# schematic.net
KiCad netlist of a schematic drawn in EAGLE
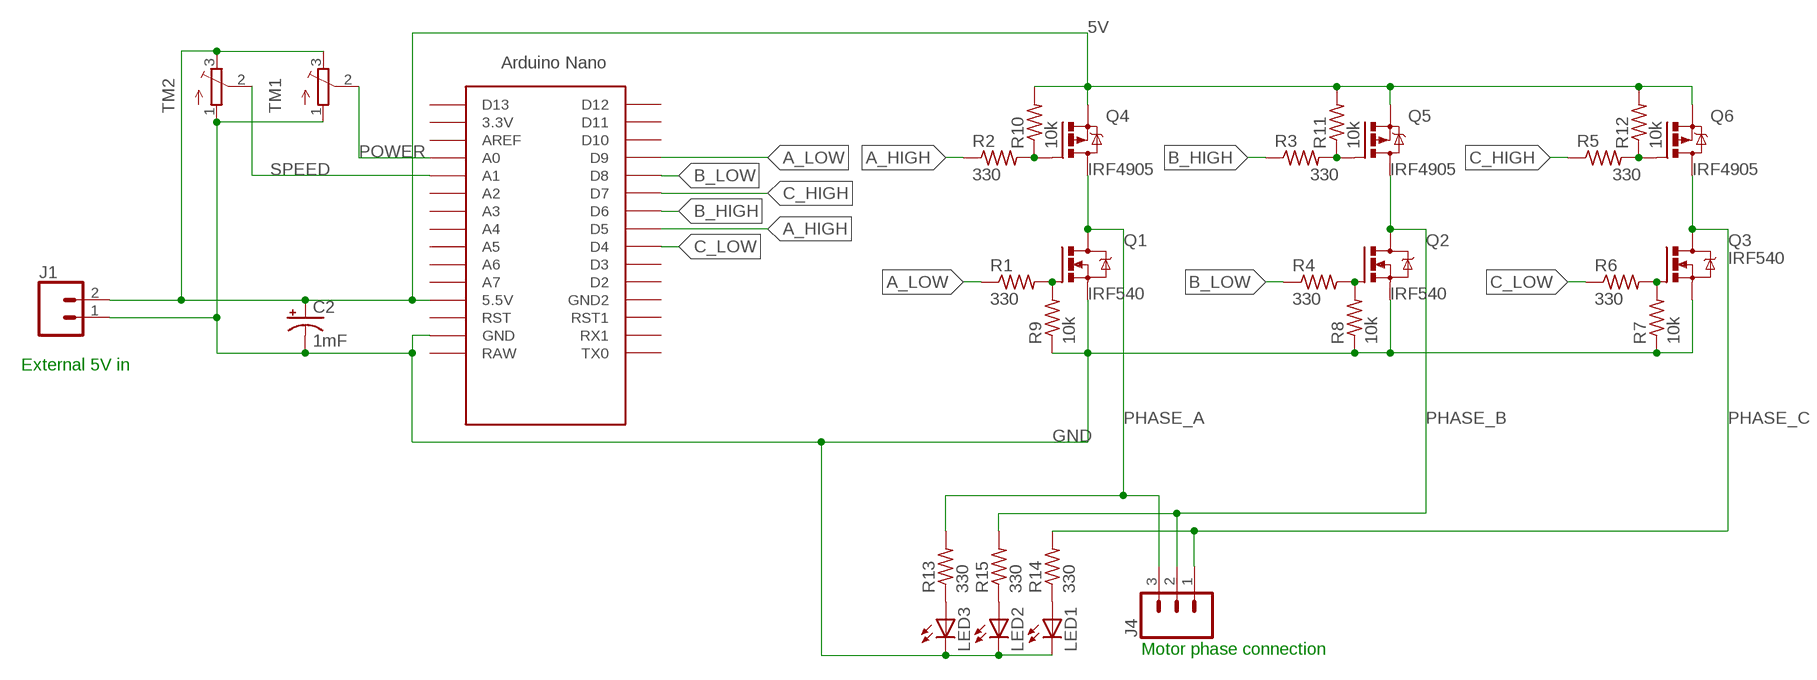
[diagram p0: schematic, sheet 1]

(export (version "E")
  (design (tool "Eeschema 10.0.6"))
  (components
    (comp (ref "C2")
      (value "1mF")
      (footprint "eagle-import:CPOL-RADIAL-5MM-10MM")
      (libsource (lib "eagle-import") (part "1000UF-RADIAL-5MM-25V-20%"))
    )
    (comp (ref "J1")
      (value "CONN_025MM")
      (footprint "eagle-import:SCREWTERMINAL-5MM-2")
      (libsource (lib "eagle-import") (part "CONN_025MM"))
    )
    (comp (ref "J4")
      (value "CONN_03-SCREW-5MM")
      (footprint "eagle-import:SCREWTERMINAL-5MM-3")
      (libsource (lib "eagle-import") (part "CONN_03-SCREW-5MM"))
    )
    (comp (ref "LED1")
      (value "LED5MM")
      (footprint "eagle-import:LED5MM")
      (libsource (lib "eagle-import") (part "LED5MM"))
    )
    (comp (ref "LED2")
      (value "LED5MM")
      (footprint "eagle-import:LED5MM")
      (libsource (lib "eagle-import") (part "LED5MM"))
    )
    (comp (ref "LED3")
      (value "LED5MM")
      (footprint "eagle-import:LED5MM")
      (libsource (lib "eagle-import") (part "LED5MM"))
    )
    (comp (ref "Q1")
      (value "IRF540")
      (footprint "eagle-import:TO220BV")
      (libsource (lib "eagle-import") (part "IRF540"))
    )
    (comp (ref "Q2")
      (value "IRF540")
      (footprint "eagle-import:TO220BV")
      (libsource (lib "eagle-import") (part "IRF540"))
    )
    (comp (ref "Q3")
      (value "IRF540")
      (footprint "eagle-import:TO220BV")
      (libsource (lib "eagle-import") (part "IRF540"))
    )
    (comp (ref "Q4")
      (value "IRF4905")
      (footprint "eagle-import:TO220BH")
      (libsource (lib "eagle-import") (part "IRF4905"))
    )
    (comp (ref "Q5")
      (value "IRF4905")
      (footprint "eagle-import:TO220BH")
      (libsource (lib "eagle-import") (part "IRF4905"))
    )
    (comp (ref "Q6")
      (value "IRF4905")
      (footprint "eagle-import:TO220BH")
      (libsource (lib "eagle-import") (part "IRF4905"))
    )
    (comp (ref "R1")
      (value "330")
      (footprint "eagle-import:0204_5")
      (libsource (lib "eagle-import") (part "R-US_0204/5"))
    )
    (comp (ref "R2")
      (value "330")
      (footprint "eagle-import:0204_5")
      (libsource (lib "eagle-import") (part "R-US_0204/5"))
    )
    (comp (ref "R3")
      (value "330")
      (footprint "eagle-import:0204_5")
      (libsource (lib "eagle-import") (part "R-US_0204/5"))
    )
    (comp (ref "R4")
      (value "330")
      (footprint "eagle-import:0204_5")
      (libsource (lib "eagle-import") (part "R-US_0204/5"))
    )
    (comp (ref "R5")
      (value "330")
      (footprint "eagle-import:0204_5")
      (libsource (lib "eagle-import") (part "R-US_0204/5"))
    )
    (comp (ref "R6")
      (value "330")
      (footprint "eagle-import:0204_5")
      (libsource (lib "eagle-import") (part "R-US_0204/5"))
    )
    (comp (ref "R7")
      (value "10k")
      (footprint "eagle-import:0204_5")
      (libsource (lib "eagle-import") (part "R-US_0204/5"))
    )
    (comp (ref "R8")
      (value "10k")
      (footprint "eagle-import:0204_5")
      (libsource (lib "eagle-import") (part "R-US_0204/5"))
    )
    (comp (ref "R9")
      (value "10k")
      (footprint "eagle-import:0204_5")
      (libsource (lib "eagle-import") (part "R-US_0204/5"))
    )
    (comp (ref "R10")
      (value "10k")
      (footprint "eagle-import:0204_5")
      (libsource (lib "eagle-import") (part "R-US_0204/5"))
    )
    (comp (ref "R11")
      (value "10k")
      (footprint "eagle-import:0204_5")
      (libsource (lib "eagle-import") (part "R-US_0204/5"))
    )
    (comp (ref "R12")
      (value "10k")
      (footprint "eagle-import:0204_5")
      (libsource (lib "eagle-import") (part "R-US_0204/5"))
    )
    (comp (ref "R13")
      (value "330")
      (footprint "eagle-import:0204_5")
      (libsource (lib "eagle-import") (part "R-US_0204/5"))
    )
    (comp (ref "R14")
      (value "330")
      (footprint "eagle-import:0204_5")
      (libsource (lib "eagle-import") (part "R-US_0204/5"))
    )
    (comp (ref "R15")
      (value "330")
      (footprint "eagle-import:0204_5")
      (libsource (lib "eagle-import") (part "R-US_0204/5"))
    )
    (comp (ref "TM1")
      (value "TRIMPOT3386")
      (footprint "eagle-import:TRIM-3386")
      (libsource (lib "eagle-import") (part "TRIMPOT3386"))
    )
    (comp (ref "TM2")
      (value "TRIMPOT3386")
      (footprint "eagle-import:TRIM-3386")
      (libsource (lib "eagle-import") (part "TRIMPOT3386"))
    )
    (comp (ref "U$1")
      (value "NANO")
      (footprint "eagle-import:NANO")
      (libsource (lib "eagle-import") (part "NANO"))
    )
  )
  (nets
    (net (code "1") (name "/5V") (class "Default")
      (node (ref "C2") (pin "+") (pinfunction "+_+") (pintype "passive"))
      (node (ref "J1") (pin "2") (pinfunction "2_2") (pintype "passive"))
      (node (ref "Q4") (pin "S") (pinfunction "S_S") (pintype "passive"))
      (node (ref "Q5") (pin "S") (pinfunction "S_S") (pintype "passive"))
      (node (ref "Q6") (pin "S") (pinfunction "S_S") (pintype "passive"))
      (node (ref "R10") (pin "2") (pinfunction "2_2") (pintype "passive"))
      (node (ref "R11") (pin "2") (pinfunction "2_2") (pintype "passive"))
      (node (ref "R12") (pin "2") (pinfunction "2_2") (pintype "passive"))
      (node (ref "TM1") (pin "3") (pinfunction "E_3") (pintype "passive"))
      (node (ref "TM2") (pin "3") (pinfunction "E_3") (pintype "passive"))
      (node (ref "U$1") (pin "5V") (pinfunction "5.5V_5V") (pintype "bidirectional"))
    )
    (net (code "2") (name "/GND") (class "Default")
      (node (ref "C2") (pin "-") (pinfunction "-_-") (pintype "passive"))
      (node (ref "J1") (pin "1") (pinfunction "1_1") (pintype "passive"))
      (node (ref "LED1") (pin "K") (pinfunction "C_K") (pintype "passive"))
      (node (ref "LED2") (pin "K") (pinfunction "C_K") (pintype "passive"))
      (node (ref "LED3") (pin "K") (pinfunction "C_K") (pintype "passive"))
      (node (ref "Q1") (pin "S") (pinfunction "S_S") (pintype "passive"))
      (node (ref "Q2") (pin "S") (pinfunction "S_S") (pintype "passive"))
      (node (ref "Q3") (pin "S") (pinfunction "S_S") (pintype "passive"))
      (node (ref "R7") (pin "1") (pinfunction "1_1") (pintype "passive"))
      (node (ref "R8") (pin "1") (pinfunction "1_1") (pintype "passive"))
      (node (ref "R9") (pin "1") (pinfunction "1_1") (pintype "passive"))
      (node (ref "TM1") (pin "1") (pinfunction "A_1") (pintype "passive"))
      (node (ref "TM2") (pin "1") (pinfunction "A_1") (pintype "passive"))
      (node (ref "U$1") (pin "GND") (pinfunction "GND_GND") (pintype "bidirectional"))
    )
    (net (code "3") (name "/PHASE_A") (class "Default")
      (node (ref "J4") (pin "3") (pinfunction "3_3") (pintype "passive"))
      (node (ref "Q1") (pin "D") (pinfunction "D_D") (pintype "passive"))
      (node (ref "Q4") (pin "D") (pinfunction "D_D") (pintype "passive"))
      (node (ref "R13") (pin "2") (pinfunction "2_2") (pintype "passive"))
    )
    (net (code "4") (name "/PHASE_B") (class "Default")
      (node (ref "J4") (pin "2") (pinfunction "2_2") (pintype "passive"))
      (node (ref "Q2") (pin "D") (pinfunction "D_D") (pintype "passive"))
      (node (ref "Q5") (pin "D") (pinfunction "D_D") (pintype "passive"))
      (node (ref "R15") (pin "2") (pinfunction "2_2") (pintype "passive"))
    )
    (net (code "5") (name "/PHASE_C") (class "Default")
      (node (ref "J4") (pin "1") (pinfunction "1_1") (pintype "passive"))
      (node (ref "Q3") (pin "D") (pinfunction "D_D") (pintype "passive"))
      (node (ref "Q6") (pin "D") (pinfunction "D_D") (pintype "passive"))
      (node (ref "R14") (pin "2") (pinfunction "2_2") (pintype "passive"))
    )
    (net (code "6") (name "/POWER") (class "Default")
      (node (ref "TM1") (pin "2") (pinfunction "S_2") (pintype "passive"))
      (node (ref "U$1") (pin "A0") (pinfunction "A0_A0") (pintype "bidirectional"))
    )
    (net (code "7") (name "/SPEED") (class "Default")
      (node (ref "TM2") (pin "2") (pinfunction "S_2") (pintype "passive"))
      (node (ref "U$1") (pin "A1") (pinfunction "A1_A1") (pintype "bidirectional"))
    )
    (net (code "8") (name "A_HIGH") (class "Default")
      (node (ref "R2") (pin "1") (pinfunction "1_1") (pintype "passive"))
      (node (ref "U$1") (pin "D5") (pinfunction "D5_D5") (pintype "bidirectional"))
    )
    (net (code "9") (name "A_LOW") (class "Default")
      (node (ref "R1") (pin "1") (pinfunction "1_1") (pintype "passive"))
      (node (ref "U$1") (pin "D9") (pinfunction "D9_D9") (pintype "bidirectional"))
    )
    (net (code "10") (name "B_HIGH") (class "Default")
      (node (ref "R3") (pin "1") (pinfunction "1_1") (pintype "passive"))
      (node (ref "U$1") (pin "D6") (pinfunction "D6_D6") (pintype "bidirectional"))
    )
    (net (code "11") (name "B_LOW") (class "Default")
      (node (ref "R4") (pin "1") (pinfunction "1_1") (pintype "passive"))
      (node (ref "U$1") (pin "D8") (pinfunction "D8_D8") (pintype "bidirectional"))
    )
    (net (code "12") (name "C_HIGH") (class "Default")
      (node (ref "R5") (pin "1") (pinfunction "1_1") (pintype "passive"))
      (node (ref "U$1") (pin "D7") (pinfunction "D7_D7") (pintype "bidirectional"))
    )
    (net (code "13") (name "C_LOW") (class "Default")
      (node (ref "R6") (pin "1") (pinfunction "1_1") (pintype "passive"))
      (node (ref "U$1") (pin "D4") (pinfunction "D4_D4") (pintype "bidirectional"))
    )
    (net (code "14") (name "Net-(LED1-PadA)") (class "Default")
      (node (ref "LED1") (pin "A") (pinfunction "A_A") (pintype "passive"))
      (node (ref "R14") (pin "1") (pinfunction "1_1") (pintype "passive"))
    )
    (net (code "15") (name "Net-(LED2-PadA)") (class "Default")
      (node (ref "LED2") (pin "A") (pinfunction "A_A") (pintype "passive"))
      (node (ref "R15") (pin "1") (pinfunction "1_1") (pintype "passive"))
    )
    (net (code "16") (name "Net-(LED3-PadA)") (class "Default")
      (node (ref "LED3") (pin "A") (pinfunction "A_A") (pintype "passive"))
      (node (ref "R13") (pin "1") (pinfunction "1_1") (pintype "passive"))
    )
    (net (code "17") (name "Net-(Q1-PadG)") (class "Default")
      (node (ref "Q1") (pin "G") (pinfunction "G_G") (pintype "passive"))
      (node (ref "R1") (pin "2") (pinfunction "2_2") (pintype "passive"))
      (node (ref "R9") (pin "2") (pinfunction "2_2") (pintype "passive"))
    )
    (net (code "18") (name "Net-(Q2-PadG)") (class "Default")
      (node (ref "Q2") (pin "G") (pinfunction "G_G") (pintype "passive"))
      (node (ref "R4") (pin "2") (pinfunction "2_2") (pintype "passive"))
      (node (ref "R8") (pin "2") (pinfunction "2_2") (pintype "passive"))
    )
    (net (code "19") (name "Net-(Q3-PadG)") (class "Default")
      (node (ref "Q3") (pin "G") (pinfunction "G_G") (pintype "passive"))
      (node (ref "R6") (pin "2") (pinfunction "2_2") (pintype "passive"))
      (node (ref "R7") (pin "2") (pinfunction "2_2") (pintype "passive"))
    )
    (net (code "20") (name "Net-(Q4-PadG)") (class "Default")
      (node (ref "Q4") (pin "G") (pinfunction "G_G") (pintype "passive"))
      (node (ref "R10") (pin "1") (pinfunction "1_1") (pintype "passive"))
      (node (ref "R2") (pin "2") (pinfunction "2_2") (pintype "passive"))
    )
    (net (code "21") (name "Net-(Q5-PadG)") (class "Default")
      (node (ref "Q5") (pin "G") (pinfunction "G_G") (pintype "passive"))
      (node (ref "R11") (pin "1") (pinfunction "1_1") (pintype "passive"))
      (node (ref "R3") (pin "2") (pinfunction "2_2") (pintype "passive"))
    )
    (net (code "22") (name "Net-(Q6-PadG)") (class "Default")
      (node (ref "Q6") (pin "G") (pinfunction "G_G") (pintype "passive"))
      (node (ref "R12") (pin "1") (pinfunction "1_1") (pintype "passive"))
      (node (ref "R5") (pin "2") (pinfunction "2_2") (pintype "passive"))
    )
    (net (code "23") (name "unconnected-(U$1-GND2-PadGND1)") (class "Default")
      (node (ref "U$1") (pin "GND1") (pinfunction "GND2_GND1") (pintype "bidirectional"))
    )
    (net (code "24") (name "unconnected-(U$1-Pad3.3V)") (class "Default")
      (node (ref "U$1") (pin "3.3V") (pinfunction "3.3V_3.3V") (pintype "bidirectional"))
    )
    (net (code "25") (name "unconnected-(U$1-PadA2)") (class "Default")
      (node (ref "U$1") (pin "A2") (pinfunction "A2_A2") (pintype "bidirectional"))
    )
    (net (code "26") (name "unconnected-(U$1-PadA3)") (class "Default")
      (node (ref "U$1") (pin "A3") (pinfunction "A3_A3") (pintype "bidirectional"))
    )
    (net (code "27") (name "unconnected-(U$1-PadA4)") (class "Default")
      (node (ref "U$1") (pin "A4") (pinfunction "A4_A4") (pintype "bidirectional"))
    )
    (net (code "28") (name "unconnected-(U$1-PadA5)") (class "Default")
      (node (ref "U$1") (pin "A5") (pinfunction "A5_A5") (pintype "bidirectional"))
    )
    (net (code "29") (name "unconnected-(U$1-PadA6)") (class "Default")
      (node (ref "U$1") (pin "A6") (pinfunction "A6_A6") (pintype "bidirectional"))
    )
    (net (code "30") (name "unconnected-(U$1-PadA7)") (class "Default")
      (node (ref "U$1") (pin "A7") (pinfunction "A7_A7") (pintype "bidirectional"))
    )
    (net (code "31") (name "unconnected-(U$1-PadAREF)") (class "Default")
      (node (ref "U$1") (pin "AREF") (pinfunction "AREF_AREF") (pintype "bidirectional"))
    )
    (net (code "32") (name "unconnected-(U$1-PadD2)") (class "Default")
      (node (ref "U$1") (pin "D2") (pinfunction "D2_D2") (pintype "bidirectional"))
    )
    (net (code "33") (name "unconnected-(U$1-PadD3)") (class "Default")
      (node (ref "U$1") (pin "D3") (pinfunction "D3_D3") (pintype "bidirectional"))
    )
    (net (code "34") (name "unconnected-(U$1-PadD10)") (class "Default")
      (node (ref "U$1") (pin "D10") (pinfunction "D10_D10") (pintype "bidirectional"))
    )
    (net (code "35") (name "unconnected-(U$1-PadD11)") (class "Default")
      (node (ref "U$1") (pin "D11") (pinfunction "D11_D11") (pintype "bidirectional"))
    )
    (net (code "36") (name "unconnected-(U$1-PadD12)") (class "Default")
      (node (ref "U$1") (pin "D12") (pinfunction "D12_D12") (pintype "bidirectional"))
    )
    (net (code "37") (name "unconnected-(U$1-PadD13)") (class "Default")
      (node (ref "U$1") (pin "D13") (pinfunction "D13_D13") (pintype "bidirectional"))
    )
    (net (code "38") (name "unconnected-(U$1-PadICSP1)") (class "Default")
      (node (ref "U$1") (pin "ICSP1") (pinfunction "ICSP1_ICSP1") (pintype "bidirectional"))
    )
    (net (code "39") (name "unconnected-(U$1-PadICSP2)") (class "Default")
      (node (ref "U$1") (pin "ICSP2") (pinfunction "ICSP2_ICSP2") (pintype "bidirectional"))
    )
    (net (code "40") (name "unconnected-(U$1-PadICSP3)") (class "Default")
      (node (ref "U$1") (pin "ICSP3") (pinfunction "ICSP3_ICSP3") (pintype "bidirectional"))
    )
    (net (code "41") (name "unconnected-(U$1-PadICSP4)") (class "Default")
      (node (ref "U$1") (pin "ICSP4") (pinfunction "ICSP4_ICSP4") (pintype "bidirectional"))
    )
    (net (code "42") (name "unconnected-(U$1-PadICSP5)") (class "Default")
      (node (ref "U$1") (pin "ICSP5") (pinfunction "ICSP5_ICSP5") (pintype "bidirectional"))
    )
    (net (code "43") (name "unconnected-(U$1-PadICSP6)") (class "Default")
      (node (ref "U$1") (pin "ICSP6") (pinfunction "ICSP6_ICSP6") (pintype "bidirectional"))
    )
    (net (code "44") (name "unconnected-(U$1-PadRAW)") (class "Default")
      (node (ref "U$1") (pin "RAW") (pinfunction "RAW_RAW") (pintype "bidirectional"))
    )
    (net (code "45") (name "unconnected-(U$1-PadRST)") (class "Default")
      (node (ref "U$1") (pin "RST") (pinfunction "RST_RST") (pintype "bidirectional"))
    )
    (net (code "46") (name "unconnected-(U$1-PadRST1)") (class "Default")
      (node (ref "U$1") (pin "RST1") (pinfunction "RST1_RST1") (pintype "bidirectional"))
    )
    (net (code "47") (name "unconnected-(U$1-PadRX1)") (class "Default")
      (node (ref "U$1") (pin "RX1") (pinfunction "RX1_RX1") (pintype "bidirectional"))
    )
    (net (code "48") (name "unconnected-(U$1-PadTX0)") (class "Default")
      (node (ref "U$1") (pin "TX0") (pinfunction "TX0_TX0") (pintype "bidirectional"))
    )
  )
)
